# 105358-3SC002-01-A_IR_extra.net
KiCad netlist of a schematic drawn in Altium Designer
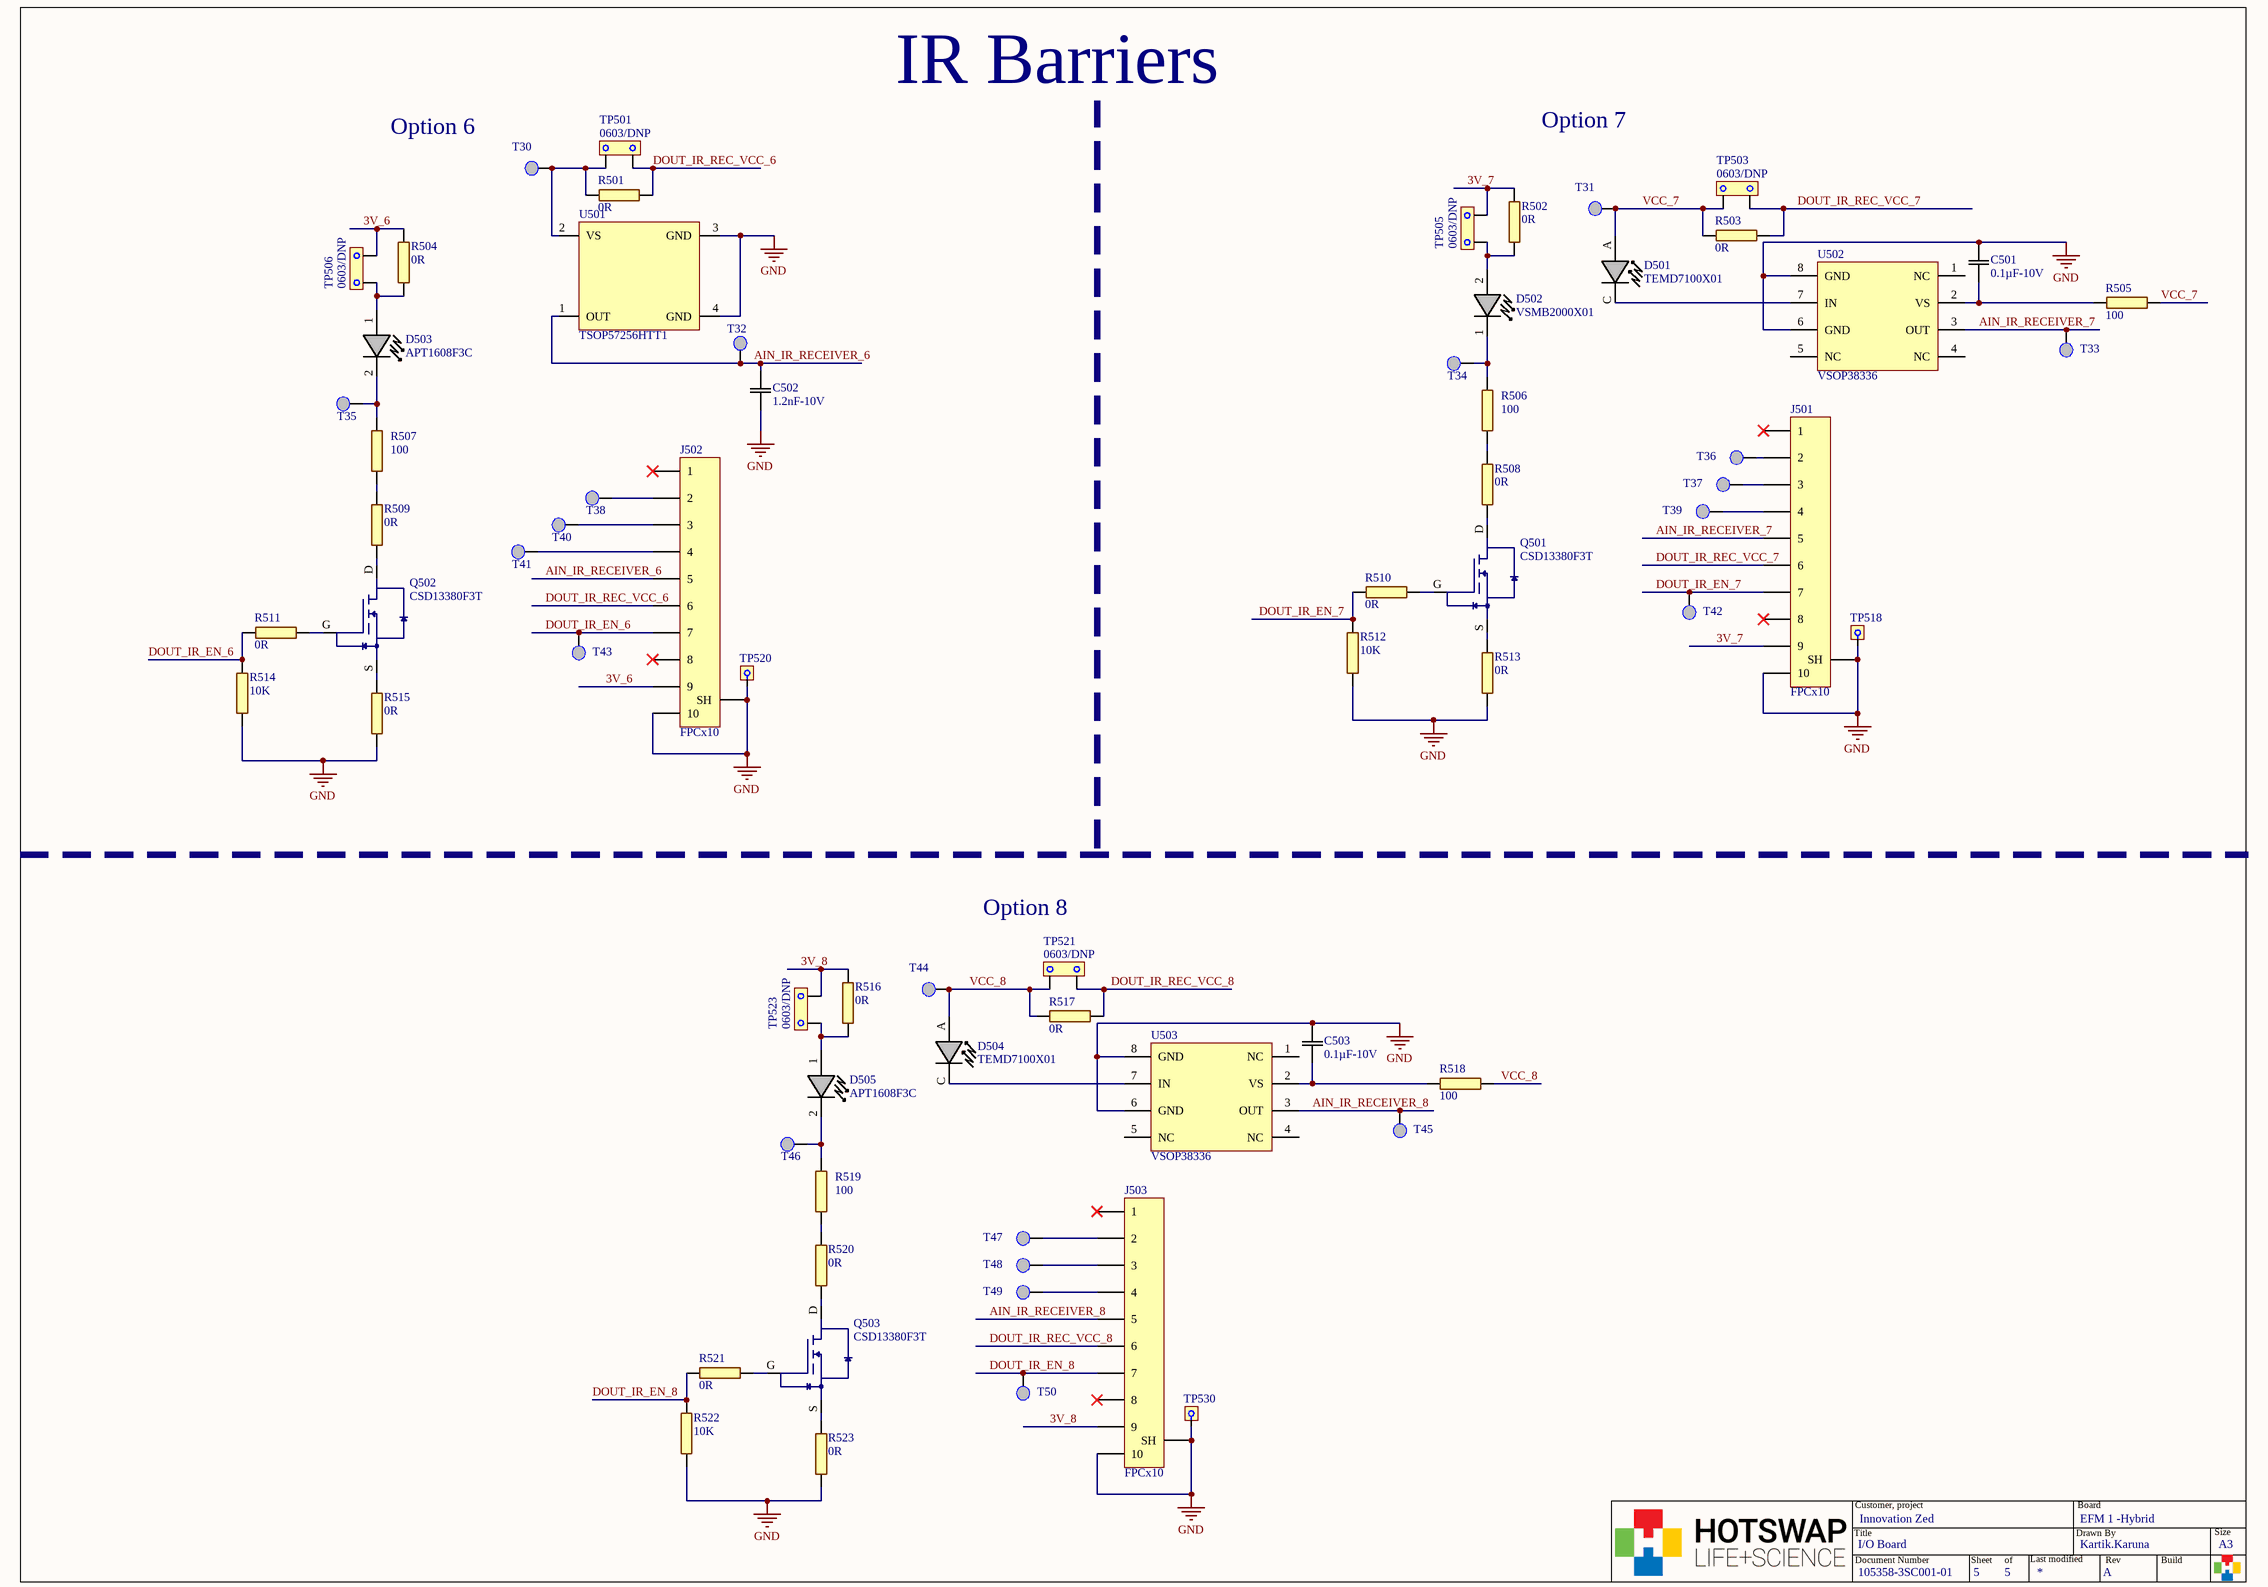
[diagram p0: 105358-3SC002-01-A_IR_extra.SchDoc]

(export (version "E")
  (design (tool "Eeschema 10.0.6"))
  (components
    (comp (ref "C501")
      (value "0.1µF-10V")
      (footprint "0402C_HIGH_DENSITY")
      (description "0.1µF ±10% 10V X5R Ceramic Capacitor 0402")
      (fields
        (field (name "MANUFACTURER PART NUMBER") "CC0402KRX5R6BB104")
        (field (name "MANUFACTURER") "Yageo")
      )
      (libsource (lib "ConnectMedical") (part "0402C-0.1uF-10V"))
    )
    (comp (ref "C502")
      (value "1.2nF-10V")
      (footprint "0402C_HIGH_DENSITY")
      (description "1.2nF ±10% 10V U2J Ceramic Capacitor 0402")
      (fields
        (field (name "MANUFACTURER PART NUMBER") "GRM1557U1A122JA01D")
        (field (name "MANUFACTURER") "Murata Electronics North America")
      )
      (libsource (lib "ConnectMedical") (part "0402C-1.2nF-10V"))
    )
    (comp (ref "C503")
      (value "0.1µF-10V")
      (footprint "0402C_HIGH_DENSITY")
      (description "0.1µF ±10% 10V X5R Ceramic Capacitor 0402")
      (fields
        (field (name "MANUFACTURER PART NUMBER") "CC0402KRX5R6BB104")
        (field (name "MANUFACTURER") "Yageo")
      )
      (libsource (lib "ConnectMedical") (part "0402C-0.1uF-10V"))
    )
    (comp (ref "D501")
      (value "TEMD7100X01")
      (footprint "TEMD7100X01")
      (description "PHOTODIODE PIN 950NM 0805")
      (fields
        (field (name "MANUFACTURER") "Vishay Semiconductor Opto Division")
        (field (name "DIGI-KEY PART NUMBER") "TEMD7100X01CT-ND")
      )
      (libsource (lib "ConnectMedical") (part "TEMD7100X01"))
    )
    (comp (ref "D502")
      (value "VSMB2000X01")
      (footprint "SODFL580X160")
      (description "EMITTER IR 940NM 100MA SMD")
      (fields
        (field (name "MANUFACTURER") "Vishay Semiconductor Opto Division")
        (field (name "DIGI-KEY PART NUMBER") "VSMB2000X01CT-ND")
      )
      (libsource (lib "ConnectMedical") (part "VSMB2000X01"))
    )
    (comp (ref "D503")
      (value "APT1608F3C")
      (footprint "APT1608F3C")
      (description "0603 INFRARED DIODE")
      (fields
        (field (name "MANUFACTURER") "Kingbright")
        (field (name "DIGI-KEY PART NUMBER") "754-1433-1-ND")
      )
      (libsource (lib "ConnectMedical") (part "APT1608F3C"))
    )
    (comp (ref "D504")
      (value "TEMD7100X01")
      (footprint "TEMD7100X01")
      (description "PHOTODIODE PIN 950NM 0805")
      (fields
        (field (name "MANUFACTURER") "Vishay Semiconductor Opto Division")
        (field (name "DIGI-KEY PART NUMBER") "TEMD7100X01CT-ND")
      )
      (libsource (lib "ConnectMedical") (part "TEMD7100X01"))
    )
    (comp (ref "D505")
      (value "APT1608F3C")
      (footprint "APT1608F3C")
      (description "0603 INFRARED DIODE")
      (fields
        (field (name "MANUFACTURER") "Kingbright")
        (field (name "DIGI-KEY PART NUMBER") "754-1433-1-ND")
      )
      (libsource (lib "ConnectMedical") (part "APT1608F3C"))
    )
    (comp (ref "J501")
      (value "FPCx10")
      (footprint "FPCx10-5034801000")
      (description "CONN FFC FPC 10POS 0.50MM R/A")
      (fields
        (field (name "MANUFACTURER PART NUMBER") "5034801000")
        (field (name "MANUFACTURER") "Molex, LLC")
      )
      (libsource (lib "ConnectMedical") (part "FPCx10"))
    )
    (comp (ref "J502")
      (value "FPCx10")
      (footprint "FPCx10-5034801000")
      (description "CONN FFC FPC 10POS 0.50MM R/A")
      (fields
        (field (name "MANUFACTURER PART NUMBER") "5034801000")
        (field (name "MANUFACTURER") "Molex, LLC")
      )
      (libsource (lib "ConnectMedical") (part "FPCx10"))
    )
    (comp (ref "J503")
      (value "FPCx10")
      (footprint "FPCx10-5034801000")
      (description "CONN FFC FPC 10POS 0.50MM R/A")
      (fields
        (field (name "MANUFACTURER PART NUMBER") "5034801000")
        (field (name "MANUFACTURER") "Molex, LLC")
      )
      (libsource (lib "ConnectMedical") (part "FPCx10"))
    )
    (comp (ref "Q501")
      (value "CSD13380F3T")
      (footprint "CSD13380F3-DFN40P69X35-3L")
      (description "12V N-CHANNEL FEMTOFET MOSFET")
      (fields (field (name "MANUFACTURER") "Texas Instruments"))
      (libsource (lib "ConnectMedical") (part "CSD13380F3T"))
    )
    (comp (ref "Q502")
      (value "CSD13380F3T")
      (footprint "CSD13380F3-DFN40P69X35-3L")
      (description "12V N-CHANNEL FEMTOFET MOSFET")
      (fields (field (name "MANUFACTURER") "Texas Instruments"))
      (libsource (lib "ConnectMedical") (part "CSD13380F3T"))
    )
    (comp (ref "Q503")
      (value "CSD13380F3T")
      (footprint "CSD13380F3-DFN40P69X35-3L")
      (description "12V N-CHANNEL FEMTOFET MOSFET")
      (fields (field (name "MANUFACTURER") "Texas Instruments"))
      (libsource (lib "ConnectMedical") (part "CSD13380F3T"))
    )
    (comp (ref "R501")
      (value "0R")
      (footprint "0603R-GENRIC")
      (description "RES SMD 0 OHM 1% 1/10W 0603")
      (fields (field (name "POWER") "0.063W"))
      (libsource (lib "") (part "0603R-0R -1%-0.063W_1"))
    )
    (comp (ref "R502")
      (value "0R")
      (footprint "0603R-GENRIC")
      (description "RES SMD 0 OHM 1% 1/10W 0603")
      (fields (field (name "POWER") "0.063W"))
      (libsource (lib "ConnectMedical") (part "0603R-0R -1%-0.063W"))
    )
    (comp (ref "R503")
      (value "0R")
      (footprint "0603R-GENRIC")
      (description "RES SMD 0 OHM 1% 1/10W 0603")
      (fields (field (name "POWER") "0.063W"))
      (libsource (lib "") (part "0603R-0R -1%-0.063W_1"))
    )
    (comp (ref "R504")
      (value "0R")
      (footprint "0603R-GENRIC")
      (description "RES SMD 0 OHM 1% 1/10W 0603")
      (fields (field (name "POWER") "0.063W"))
      (libsource (lib "ConnectMedical") (part "0603R-0R -1%-0.063W"))
    )
    (comp (ref "R505")
      (value "100")
      (footprint "0402R-GENERIC")
      (description "RES SMD 100OHM 1% 1/16W 0402")
      (fields (field (name "DIGI-KEY PART NUMBER") "311-100LRCT-ND") (field (name "MANUFACTURER") "Yageo"))
      (libsource (lib "ConnectMedical") (part "0402R-100 OHM-1%-0.063W"))
    )
    (comp (ref "R506")
      (value "100")
      (footprint "0402R-GENERIC")
      (description "RES SMD 100OHM 1% 1/16W 0402")
      (fields (field (name "DIGI-KEY PART NUMBER") "311-100LRCT-ND") (field (name "MANUFACTURER") "Yageo"))
      (libsource (lib "") (part "0402R-100 OHM-1%-0.063W_1"))
    )
    (comp (ref "R507")
      (value "100")
      (footprint "0402R-GENERIC")
      (description "RES SMD 100OHM 1% 1/16W 0402")
      (fields (field (name "DIGI-KEY PART NUMBER") "311-100LRCT-ND") (field (name "MANUFACTURER") "Yageo"))
      (libsource (lib "") (part "0402R-100 OHM-1%-0.063W_1"))
    )
    (comp (ref "R508")
      (value "0R")
      (footprint "0603R-GENRIC")
      (description "RES SMD 0 OHM 1% 1/10W 0603")
      (fields (field (name "POWER") "0.063W"))
      (libsource (lib "") (part "0603R-0R -1%-0.063W_2"))
    )
    (comp (ref "R509")
      (value "0R")
      (footprint "0603R-GENRIC")
      (description "RES SMD 0 OHM 1% 1/10W 0603")
      (fields (field (name "POWER") "0.063W"))
      (libsource (lib "") (part "0603R-0R -1%-0.063W_2"))
    )
    (comp (ref "R510")
      (value "0R")
      (footprint "0603R-GENRIC")
      (description "RES SMD 0 OHM 1% 1/10W 0603")
      (fields (field (name "POWER") "0.063W"))
      (libsource (lib "") (part "0603R-0R -1%-0.063W_1"))
    )
    (comp (ref "R511")
      (value "0R")
      (footprint "0603R-GENRIC")
      (description "RES SMD 0 OHM 1% 1/10W 0603")
      (fields (field (name "POWER") "0.063W"))
      (libsource (lib "") (part "0603R-0R -1%-0.063W_1"))
    )
    (comp (ref "R512")
      (value "10K")
      (footprint "0402R-GENERIC")
      (description "RES SMD 10kOHM 1% 1/16W 0402")
      (fields (field (name "DIGI-KEY PART NUMBER") "311-10.0KLRCT-ND") (field (name "MANUFACTURER") "Yageo"))
      (libsource (lib "ConnectMedical") (part "0402R-10k OHM-1%-0.063W"))
    )
    (comp (ref "R513")
      (value "0R")
      (footprint "0603R-GENRIC")
      (description "RES SMD 0 OHM 1% 1/10W 0603")
      (fields (field (name "POWER") "0.063W"))
      (libsource (lib "ConnectMedical") (part "0603R-0R -1%-0.063W"))
    )
    (comp (ref "R514")
      (value "10K")
      (footprint "0402R-GENERIC")
      (description "RES SMD 10kOHM 1% 1/16W 0402")
      (fields (field (name "DIGI-KEY PART NUMBER") "311-10.0KLRCT-ND") (field (name "MANUFACTURER") "Yageo"))
      (libsource (lib "ConnectMedical") (part "0402R-10k OHM-1%-0.063W"))
    )
    (comp (ref "R515")
      (value "0R")
      (footprint "0603R-GENRIC")
      (description "RES SMD 0 OHM 1% 1/10W 0603")
      (fields (field (name "POWER") "0.063W"))
      (libsource (lib "ConnectMedical") (part "0603R-0R -1%-0.063W"))
    )
    (comp (ref "R516")
      (value "0R")
      (footprint "0603R-GENRIC")
      (description "RES SMD 0 OHM 1% 1/10W 0603")
      (fields (field (name "POWER") "0.063W"))
      (libsource (lib "ConnectMedical") (part "0603R-0R -1%-0.063W"))
    )
    (comp (ref "R517")
      (value "0R")
      (footprint "0603R-GENRIC")
      (description "RES SMD 0 OHM 1% 1/10W 0603")
      (fields (field (name "POWER") "0.063W"))
      (libsource (lib "") (part "0603R-0R -1%-0.063W_1"))
    )
    (comp (ref "R518")
      (value "100")
      (footprint "0402R-GENERIC")
      (description "RES SMD 100OHM 1% 1/16W 0402")
      (fields (field (name "DIGI-KEY PART NUMBER") "311-100LRCT-ND") (field (name "MANUFACTURER") "Yageo"))
      (libsource (lib "ConnectMedical") (part "0402R-100 OHM-1%-0.063W"))
    )
    (comp (ref "R519")
      (value "100")
      (footprint "0402R-GENERIC")
      (description "RES SMD 100OHM 1% 1/16W 0402")
      (fields (field (name "DIGI-KEY PART NUMBER") "311-100LRCT-ND") (field (name "MANUFACTURER") "Yageo"))
      (libsource (lib "") (part "0402R-100 OHM-1%-0.063W_1"))
    )
    (comp (ref "R520")
      (value "0R")
      (footprint "0603R-GENRIC")
      (description "RES SMD 0 OHM 1% 1/10W 0603")
      (fields (field (name "POWER") "0.063W"))
      (libsource (lib "") (part "0603R-0R -1%-0.063W_2"))
    )
    (comp (ref "R521")
      (value "0R")
      (footprint "0603R-GENRIC")
      (description "RES SMD 0 OHM 1% 1/10W 0603")
      (fields (field (name "POWER") "0.063W"))
      (libsource (lib "") (part "0603R-0R -1%-0.063W_1"))
    )
    (comp (ref "R522")
      (value "10K")
      (footprint "0402R-GENERIC")
      (description "RES SMD 10kOHM 1% 1/16W 0402")
      (fields (field (name "DIGI-KEY PART NUMBER") "311-10.0KLRCT-ND") (field (name "MANUFACTURER") "Yageo"))
      (libsource (lib "ConnectMedical") (part "0402R-10k OHM-1%-0.063W"))
    )
    (comp (ref "R523")
      (value "0R")
      (footprint "0603R-GENRIC")
      (description "RES SMD 0 OHM 1% 1/10W 0603")
      (fields (field (name "POWER") "0.063W"))
      (libsource (lib "ConnectMedical") (part "0603R-0R -1%-0.063W"))
    )
    (comp (ref "T30")
      (value "TEST POINT")
      (footprint "PAD TEST POINT")
      (description "Testing Poiny")
      (libsource (lib "ConnectMedical") (part "TEST POINT"))
    )
    (comp (ref "T31")
      (value "TEST POINT")
      (footprint "PAD TEST POINT")
      (description "Testing Poiny")
      (libsource (lib "ConnectMedical") (part "TEST POINT"))
    )
    (comp (ref "T32")
      (value "TEST POINT")
      (footprint "PAD TEST POINT")
      (description "Testing Poiny")
      (libsource (lib "ConnectMedical") (part "TEST POINT"))
    )
    (comp (ref "T33")
      (value "TEST POINT")
      (footprint "PAD TEST POINT")
      (description "Testing Poiny")
      (libsource (lib "ConnectMedical") (part "TEST POINT"))
    )
    (comp (ref "T34")
      (value "TEST POINT")
      (footprint "PAD TEST POINT")
      (description "Testing Poiny")
      (libsource (lib "ConnectMedical") (part "TEST POINT"))
    )
    (comp (ref "T35")
      (value "TEST POINT")
      (footprint "PAD TEST POINT")
      (description "Testing Poiny")
      (libsource (lib "ConnectMedical") (part "TEST POINT"))
    )
    (comp (ref "T36")
      (value "TEST POINT")
      (footprint "PAD TEST POINT")
      (description "Testing Poiny")
      (libsource (lib "ConnectMedical") (part "TEST POINT"))
    )
    (comp (ref "T37")
      (value "TEST POINT")
      (footprint "PAD TEST POINT")
      (description "Testing Poiny")
      (libsource (lib "ConnectMedical") (part "TEST POINT"))
    )
    (comp (ref "T38")
      (value "TEST POINT")
      (footprint "PAD TEST POINT")
      (description "Testing Poiny")
      (libsource (lib "ConnectMedical") (part "TEST POINT"))
    )
    (comp (ref "T39")
      (value "TEST POINT")
      (footprint "PAD TEST POINT")
      (description "Testing Poiny")
      (libsource (lib "ConnectMedical") (part "TEST POINT"))
    )
    (comp (ref "T40")
      (value "TEST POINT")
      (footprint "PAD TEST POINT")
      (description "Testing Poiny")
      (libsource (lib "ConnectMedical") (part "TEST POINT"))
    )
    (comp (ref "T41")
      (value "TEST POINT")
      (footprint "PAD TEST POINT")
      (description "Testing Poiny")
      (libsource (lib "ConnectMedical") (part "TEST POINT"))
    )
    (comp (ref "T42")
      (value "TEST POINT")
      (footprint "PAD TEST POINT")
      (description "Testing Poiny")
      (libsource (lib "ConnectMedical") (part "TEST POINT"))
    )
    (comp (ref "T43")
      (value "TEST POINT")
      (footprint "PAD TEST POINT")
      (description "Testing Poiny")
      (libsource (lib "ConnectMedical") (part "TEST POINT"))
    )
    (comp (ref "T44")
      (value "TEST POINT")
      (footprint "PAD TEST POINT")
      (description "Testing Poiny")
      (libsource (lib "ConnectMedical") (part "TEST POINT"))
    )
    (comp (ref "T45")
      (value "TEST POINT")
      (footprint "PAD TEST POINT")
      (description "Testing Poiny")
      (libsource (lib "ConnectMedical") (part "TEST POINT"))
    )
    (comp (ref "T46")
      (value "TEST POINT")
      (footprint "PAD TEST POINT")
      (description "Testing Poiny")
      (libsource (lib "ConnectMedical") (part "TEST POINT"))
    )
    (comp (ref "T47")
      (value "TEST POINT")
      (footprint "PAD TEST POINT")
      (description "Testing Poiny")
      (libsource (lib "ConnectMedical") (part "TEST POINT"))
    )
    (comp (ref "T48")
      (value "TEST POINT")
      (footprint "PAD TEST POINT")
      (description "Testing Poiny")
      (libsource (lib "ConnectMedical") (part "TEST POINT"))
    )
    (comp (ref "T49")
      (value "TEST POINT")
      (footprint "PAD TEST POINT")
      (description "Testing Poiny")
      (libsource (lib "ConnectMedical") (part "TEST POINT"))
    )
    (comp (ref "T50")
      (value "TEST POINT")
      (footprint "PAD TEST POINT")
      (description "Testing Poiny")
      (libsource (lib "ConnectMedical") (part "TEST POINT"))
    )
    (comp (ref "TP501")
      (value "0603/DNP")
      (footprint "TESTPOINT_C_R0608")
      (description "Test point for Med Current 0402 JUMPER SMD O OHM 1% 1/4W 0603")
      (libsource (lib "") (part "TP_C_R0603_1"))
    )
    (comp (ref "TP503")
      (value "0603/DNP")
      (footprint "TESTPOINT_C_R0608")
      (description "Test point for Med Current 0402 JUMPER SMD O OHM 1% 1/4W 0603")
      (libsource (lib "") (part "TP_C_R0603_1"))
    )
    (comp (ref "TP505")
      (value "0603/DNP")
      (footprint "TESTPOINT_C_R0608")
      (description "Test point for Med Current 0402 JUMPER SMD O OHM 1% 1/4W 0603")
      (libsource (lib "ConnectMedical") (part "TP_C_R0603"))
    )
    (comp (ref "TP506")
      (value "0603/DNP")
      (footprint "TESTPOINT_C_R0608")
      (description "Test point for Med Current 0402 JUMPER SMD O OHM 1% 1/4W 0603")
      (libsource (lib "ConnectMedical") (part "TP_C_R0603"))
    )
    (comp (ref "TP518")
      (value "TP_V_HOOK")
      (footprint "Testpoint_Hook")
      (description "Black PC Test Point")
      (fields
        (field (name "DIGI-KEY PART NUMBER") "36-5001-ND")
        (field (name "MANUFACTURER") "Keystone Electronics")
      )
      (libsource (lib "ConnectMedical") (part "TP_V_HOOK"))
    )
    (comp (ref "TP520")
      (value "TP_V_HOOK")
      (footprint "Testpoint_Hook")
      (description "Black PC Test Point")
      (fields
        (field (name "DIGI-KEY PART NUMBER") "36-5001-ND")
        (field (name "MANUFACTURER") "Keystone Electronics")
      )
      (libsource (lib "ConnectMedical") (part "TP_V_HOOK"))
    )
    (comp (ref "TP521")
      (value "0603/DNP")
      (footprint "TESTPOINT_C_R0608")
      (description "Test point for Med Current 0402 JUMPER SMD O OHM 1% 1/4W 0603")
      (libsource (lib "") (part "TP_C_R0603_1"))
    )
    (comp (ref "TP523")
      (value "0603/DNP")
      (footprint "TESTPOINT_C_R0608")
      (description "Test point for Med Current 0402 JUMPER SMD O OHM 1% 1/4W 0603")
      (libsource (lib "ConnectMedical") (part "TP_C_R0603"))
    )
    (comp (ref "TP530")
      (value "TP_V_HOOK")
      (footprint "Testpoint_Hook")
      (description "Black PC Test Point")
      (fields
        (field (name "DIGI-KEY PART NUMBER") "36-5001-ND")
        (field (name "MANUFACTURER") "Keystone Electronics")
      )
      (libsource (lib "ConnectMedical") (part "TP_V_HOOK"))
    )
    (comp (ref "U501")
      (value "TSOP57256HTT1")
      (footprint "TSOP57256HTT1")
      (description "MOD IR RCVR 56KHZ TOP VIEW SHIEL")
      (fields
        (field (name "MANUFACTURER") "Vishay Semiconductor Opto Division")
        (field (name "DIGI-KEY PART NUMBER") "TSOP57256HTT1-ND")
      )
      (libsource (lib "ConnectMedical") (part "TSOP57256HTT1"))
    )
    (comp (ref "U502")
      (value "VSOP38336")
      (footprint "VSOP38336")
      (description "IC SIGNAL CONDITIONING 36KHZ QFN")
      (fields
        (field (name "MANUFACTURER") "Vishay Semiconductor Opto Division")
        (field (name "DIGI-KEY PART NUMBER") "VSOP38336CT-ND")
      )
      (libsource (lib "ConnectMedical") (part "VSOP38336"))
    )
    (comp (ref "U503")
      (value "VSOP38336")
      (footprint "VSOP38336")
      (description "IC SIGNAL CONDITIONING 36KHZ QFN")
      (fields
        (field (name "MANUFACTURER") "Vishay Semiconductor Opto Division")
        (field (name "DIGI-KEY PART NUMBER") "VSOP38336CT-ND")
      )
      (libsource (lib "ConnectMedical") (part "VSOP38336"))
    )
  )
  (nets
    (net (code "1") (name "/3V_6") (class "Default")
      (node (ref "J502") (pin "9") (pinfunction "9_9") (pintype "passive"))
      (node (ref "R504") (pin "2") (pintype "passive"))
      (node (ref "TP506") (pin "2") (pintype "power_in"))
    )
    (net (code "2") (name "/3V_7") (class "Default")
      (node (ref "J501") (pin "9") (pinfunction "9_9") (pintype "passive"))
      (node (ref "R502") (pin "2") (pintype "passive"))
      (node (ref "TP505") (pin "2") (pintype "power_in"))
    )
    (net (code "3") (name "/3V_8") (class "Default")
      (node (ref "J503") (pin "9") (pinfunction "9_9") (pintype "passive"))
      (node (ref "R516") (pin "2") (pintype "passive"))
      (node (ref "TP523") (pin "2") (pintype "power_in"))
    )
    (net (code "4") (name "/AIN_IR_RECEIVER_6") (class "Default")
      (node (ref "C502") (pin "2") (pinfunction "2_2") (pintype "passive"))
      (node (ref "J502") (pin "5") (pinfunction "5_5") (pintype "passive"))
      (node (ref "T32") (pin "1") (pinfunction "Test_Point_1") (pintype "passive"))
      (node (ref "U501") (pin "1") (pinfunction "OUT_1") (pintype "power_in"))
    )
    (net (code "5") (name "/AIN_IR_RECEIVER_7") (class "Default")
      (node (ref "J501") (pin "5") (pinfunction "5_5") (pintype "passive"))
      (node (ref "T33") (pin "1") (pinfunction "Test_Point_1") (pintype "passive"))
      (node (ref "U502") (pin "3") (pinfunction "OUT_3") (pintype "passive"))
    )
    (net (code "6") (name "/AIN_IR_RECEIVER_8") (class "Default")
      (node (ref "J503") (pin "5") (pinfunction "5_5") (pintype "passive"))
      (node (ref "T45") (pin "1") (pinfunction "Test_Point_1") (pintype "passive"))
      (node (ref "U503") (pin "3") (pinfunction "OUT_3") (pintype "passive"))
    )
    (net (code "7") (name "/DOUT_IR_EN_6") (class "Default")
      (node (ref "J502") (pin "7") (pinfunction "7_7") (pintype "passive"))
      (node (ref "R511") (pin "1") (pintype "passive"))
      (node (ref "R514") (pin "1") (pintype "passive"))
      (node (ref "T43") (pin "1") (pinfunction "Test_Point_1") (pintype "passive"))
    )
    (net (code "8") (name "/DOUT_IR_EN_7") (class "Default")
      (node (ref "J501") (pin "7") (pinfunction "7_7") (pintype "passive"))
      (node (ref "R510") (pin "1") (pintype "passive"))
      (node (ref "R512") (pin "1") (pintype "passive"))
      (node (ref "T42") (pin "1") (pinfunction "Test_Point_1") (pintype "passive"))
    )
    (net (code "9") (name "/DOUT_IR_EN_8") (class "Default")
      (node (ref "J503") (pin "7") (pinfunction "7_7") (pintype "passive"))
      (node (ref "R521") (pin "1") (pintype "passive"))
      (node (ref "R522") (pin "1") (pintype "passive"))
      (node (ref "T50") (pin "1") (pinfunction "Test_Point_1") (pintype "passive"))
    )
    (net (code "10") (name "/DOUT_IR_REC_VCC_6") (class "Default")
      (node (ref "J502") (pin "6") (pinfunction "6_6") (pintype "passive"))
      (node (ref "R501") (pin "2") (pintype "passive"))
      (node (ref "TP501") (pin "2") (pintype "power_in"))
    )
    (net (code "11") (name "/DOUT_IR_REC_VCC_7") (class "Default")
      (node (ref "J501") (pin "6") (pinfunction "6_6") (pintype "passive"))
      (node (ref "R503") (pin "2") (pintype "passive"))
      (node (ref "TP503") (pin "2") (pintype "power_in"))
    )
    (net (code "12") (name "/DOUT_IR_REC_VCC_8") (class "Default")
      (node (ref "J503") (pin "6") (pinfunction "6_6") (pintype "passive"))
      (node (ref "R517") (pin "2") (pintype "passive"))
      (node (ref "TP521") (pin "2") (pintype "power_in"))
    )
    (net (code "13") (name "/VCC_7") (class "Default")
      (node (ref "D501") (pin "A") (pinfunction "A_A") (pintype "passive"))
      (node (ref "R503") (pin "1") (pintype "passive"))
      (node (ref "R505") (pin "2") (pintype "passive"))
      (node (ref "T31") (pin "1") (pinfunction "Test_Point_1") (pintype "passive"))
      (node (ref "TP503") (pin "1") (pintype "power_in"))
    )
    (net (code "14") (name "/VCC_8") (class "Default")
      (node (ref "D504") (pin "A") (pinfunction "A_A") (pintype "passive"))
      (node (ref "R517") (pin "1") (pintype "passive"))
      (node (ref "R518") (pin "2") (pintype "passive"))
      (node (ref "T44") (pin "1") (pinfunction "Test_Point_1") (pintype "passive"))
      (node (ref "TP521") (pin "1") (pintype "power_in"))
    )
    (net (code "15") (name "GND") (class "Default")
      (node (ref "C501") (pin "2") (pinfunction "2_2") (pintype "passive"))
      (node (ref "C502") (pin "1") (pinfunction "1_1") (pintype "passive"))
      (node (ref "C503") (pin "2") (pinfunction "2_2") (pintype "passive"))
      (node (ref "J501") (pin "10") (pinfunction "10_10") (pintype "passive"))
      (node (ref "J501") (pin "SH") (pinfunction "SH_SH") (pintype "passive"))
      (node (ref "J502") (pin "10") (pinfunction "10_10") (pintype "passive"))
      (node (ref "J502") (pin "SH") (pinfunction "SH_SH") (pintype "passive"))
      (node (ref "J503") (pin "10") (pinfunction "10_10") (pintype "passive"))
      (node (ref "J503") (pin "SH") (pinfunction "SH_SH") (pintype "passive"))
      (node (ref "R512") (pin "2") (pintype "passive"))
      (node (ref "R513") (pin "1") (pintype "passive"))
      (node (ref "R514") (pin "2") (pintype "passive"))
      (node (ref "R515") (pin "1") (pintype "passive"))
      (node (ref "R522") (pin "2") (pintype "passive"))
      (node (ref "R523") (pin "1") (pintype "passive"))
      (node (ref "TP518") (pin "1") (pinfunction "8_1") (pintype "passive"))
      (node (ref "TP520") (pin "1") (pinfunction "8_1") (pintype "passive"))
      (node (ref "TP530") (pin "1") (pinfunction "8_1") (pintype "passive"))
      (node (ref "U501") (pin "3") (pinfunction "GND_3") (pintype "passive"))
      (node (ref "U501") (pin "4") (pinfunction "GND_4") (pintype "passive"))
      (node (ref "U502") (pin "6") (pinfunction "GND_6") (pintype "passive"))
      (node (ref "U502") (pin "8") (pinfunction "GND_8") (pintype "passive"))
      (node (ref "U503") (pin "6") (pinfunction "GND_6") (pintype "passive"))
      (node (ref "U503") (pin "8") (pinfunction "GND_8") (pintype "passive"))
    )
    (net (code "16") (name "Net-(D502-A)") (class "Default")
      (node (ref "D502") (pin "2") (pinfunction "A_2") (pintype "passive"))
      (node (ref "R502") (pin "1") (pintype "passive"))
      (node (ref "TP505") (pin "1") (pintype "power_in"))
    )
    (net (code "17") (name "Net-(D502-C)") (class "Default")
      (node (ref "D502") (pin "1") (pinfunction "C_1") (pintype "passive"))
      (node (ref "R506") (pin "1") (pintype "passive"))
      (node (ref "T34") (pin "1") (pinfunction "Test_Point_1") (pintype "passive"))
    )
    (net (code "18") (name "Net-(D503-A)") (class "Default")
      (node (ref "D503") (pin "1") (pinfunction "A_1") (pintype "passive"))
      (node (ref "R504") (pin "1") (pintype "passive"))
      (node (ref "TP506") (pin "1") (pintype "power_in"))
    )
    (net (code "19") (name "Net-(D503-K)") (class "Default")
      (node (ref "D503") (pin "2") (pinfunction "K_2") (pintype "passive"))
      (node (ref "R507") (pin "1") (pintype "passive"))
      (node (ref "T35") (pin "1") (pinfunction "Test_Point_1") (pintype "passive"))
    )
    (net (code "20") (name "Net-(D505-A)") (class "Default")
      (node (ref "D505") (pin "1") (pinfunction "A_1") (pintype "passive"))
      (node (ref "R516") (pin "1") (pintype "passive"))
      (node (ref "TP523") (pin "1") (pintype "power_in"))
    )
    (net (code "21") (name "Net-(D505-K)") (class "Default")
      (node (ref "D505") (pin "2") (pinfunction "K_2") (pintype "passive"))
      (node (ref "R519") (pin "1") (pintype "passive"))
      (node (ref "T46") (pin "1") (pinfunction "Test_Point_1") (pintype "passive"))
    )
    (net (code "22") (name "Net-(Q501-1)") (class "Default")
      (node (ref "Q501") (pin "G") (pinfunction "1_G") (pintype "passive"))
      (node (ref "R510") (pin "2") (pintype "passive"))
    )
    (net (code "23") (name "Net-(Q501-2)") (class "Default")
      (node (ref "Q501") (pin "S") (pinfunction "2_S") (pintype "passive"))
      (node (ref "R513") (pin "2") (pintype "passive"))
    )
    (net (code "24") (name "Net-(Q501-3)") (class "Default")
      (node (ref "Q501") (pin "D") (pinfunction "3_D") (pintype "passive"))
      (node (ref "R508") (pin "2") (pintype "passive"))
    )
    (net (code "25") (name "Net-(Q502-1)") (class "Default")
      (node (ref "Q502") (pin "G") (pinfunction "1_G") (pintype "passive"))
      (node (ref "R511") (pin "2") (pintype "passive"))
    )
    (net (code "26") (name "Net-(Q502-2)") (class "Default")
      (node (ref "Q502") (pin "S") (pinfunction "2_S") (pintype "passive"))
      (node (ref "R515") (pin "2") (pintype "passive"))
    )
    (net (code "27") (name "Net-(Q502-3)") (class "Default")
      (node (ref "Q502") (pin "D") (pinfunction "3_D") (pintype "passive"))
      (node (ref "R509") (pin "2") (pintype "passive"))
    )
    (net (code "28") (name "Net-(Q503-1)") (class "Default")
      (node (ref "Q503") (pin "G") (pinfunction "1_G") (pintype "passive"))
      (node (ref "R521") (pin "2") (pintype "passive"))
    )
    (net (code "29") (name "Net-(Q503-2)") (class "Default")
      (node (ref "Q503") (pin "S") (pinfunction "2_S") (pintype "passive"))
      (node (ref "R523") (pin "2") (pintype "passive"))
    )
    (net (code "30") (name "Net-(Q503-3)") (class "Default")
      (node (ref "Q503") (pin "D") (pinfunction "3_D") (pintype "passive"))
      (node (ref "R520") (pin "2") (pintype "passive"))
    )
    (net (code "31") (name "Net-(R506-Pad2)") (class "Default")
      (node (ref "R506") (pin "2") (pintype "passive"))
      (node (ref "R508") (pin "1") (pintype "passive"))
    )
    (net (code "32") (name "Net-(R507-Pad2)") (class "Default")
      (node (ref "R507") (pin "2") (pintype "passive"))
      (node (ref "R509") (pin "1") (pintype "passive"))
    )
    (net (code "33") (name "Net-(R519-Pad2)") (class "Default")
      (node (ref "R519") (pin "2") (pintype "passive"))
      (node (ref "R520") (pin "1") (pintype "passive"))
    )
    (net (code "34") (name "Net-(T30-Test_Point)") (class "Default")
      (node (ref "R501") (pin "1") (pintype "passive"))
      (node (ref "T30") (pin "1") (pinfunction "Test_Point_1") (pintype "passive"))
      (node (ref "TP501") (pin "1") (pintype "power_in"))
      (node (ref "U501") (pin "2") (pinfunction "VS_2") (pintype "passive"))
    )
    (net (code "35") (name "Net-(T36-Test_Point)") (class "Default")
      (node (ref "J501") (pin "2") (pinfunction "2_2") (pintype "passive"))
      (node (ref "T36") (pin "1") (pinfunction "Test_Point_1") (pintype "passive"))
    )
    (net (code "36") (name "Net-(T37-Test_Point)") (class "Default")
      (node (ref "J501") (pin "3") (pinfunction "3_3") (pintype "passive"))
      (node (ref "T37") (pin "1") (pinfunction "Test_Point_1") (pintype "passive"))
    )
    (net (code "37") (name "Net-(T38-Test_Point)") (class "Default")
      (node (ref "J502") (pin "2") (pinfunction "2_2") (pintype "passive"))
      (node (ref "T38") (pin "1") (pinfunction "Test_Point_1") (pintype "passive"))
    )
    (net (code "38") (name "Net-(T39-Test_Point)") (class "Default")
      (node (ref "J501") (pin "4") (pinfunction "4_4") (pintype "passive"))
      (node (ref "T39") (pin "1") (pinfunction "Test_Point_1") (pintype "passive"))
    )
    (net (code "39") (name "Net-(T40-Test_Point)") (class "Default")
      (node (ref "J502") (pin "3") (pinfunction "3_3") (pintype "passive"))
      (node (ref "T40") (pin "1") (pinfunction "Test_Point_1") (pintype "passive"))
    )
    (net (code "40") (name "Net-(T41-Test_Point)") (class "Default")
      (node (ref "J502") (pin "4") (pinfunction "4_4") (pintype "passive"))
      (node (ref "T41") (pin "1") (pinfunction "Test_Point_1") (pintype "passive"))
    )
    (net (code "41") (name "Net-(T47-Test_Point)") (class "Default")
      (node (ref "J503") (pin "2") (pinfunction "2_2") (pintype "passive"))
      (node (ref "T47") (pin "1") (pinfunction "Test_Point_1") (pintype "passive"))
    )
    (net (code "42") (name "Net-(T48-Test_Point)") (class "Default")
      (node (ref "J503") (pin "3") (pinfunction "3_3") (pintype "passive"))
      (node (ref "T48") (pin "1") (pinfunction "Test_Point_1") (pintype "passive"))
    )
    (net (code "43") (name "Net-(T49-Test_Point)") (class "Default")
      (node (ref "J503") (pin "4") (pinfunction "4_4") (pintype "passive"))
      (node (ref "T49") (pin "1") (pinfunction "Test_Point_1") (pintype "passive"))
    )
    (net (code "44") (name "Net-(U502-IN)") (class "Default")
      (node (ref "D501") (pin "C") (pinfunction "C_C") (pintype "passive"))
      (node (ref "U502") (pin "7") (pinfunction "IN_7") (pintype "passive"))
    )
    (net (code "45") (name "Net-(U502-VS)") (class "Default")
      (node (ref "C501") (pin "1") (pinfunction "1_1") (pintype "passive"))
      (node (ref "R505") (pin "1") (pintype "passive"))
      (node (ref "U502") (pin "2") (pinfunction "VS_2") (pintype "passive"))
    )
    (net (code "46") (name "Net-(U503-IN)") (class "Default")
      (node (ref "D504") (pin "C") (pinfunction "C_C") (pintype "passive"))
      (node (ref "U503") (pin "7") (pinfunction "IN_7") (pintype "passive"))
    )
    (net (code "47") (name "Net-(U503-VS)") (class "Default")
      (node (ref "C503") (pin "1") (pinfunction "1_1") (pintype "passive"))
      (node (ref "R518") (pin "1") (pintype "passive"))
      (node (ref "U503") (pin "2") (pinfunction "VS_2") (pintype "passive"))
    )
    (net (code "48") (name "unconnected-(J501-Pad1)") (class "Default")
      (node (ref "J501") (pin "1") (pinfunction "1_1") (pintype "passive+no_connect"))
    )
    (net (code "49") (name "unconnected-(J501-Pad8)") (class "Default")
      (node (ref "J501") (pin "8") (pinfunction "8_8") (pintype "passive+no_connect"))
    )
    (net (code "50") (name "unconnected-(J502-Pad1)") (class "Default")
      (node (ref "J502") (pin "1") (pinfunction "1_1") (pintype "passive+no_connect"))
    )
    (net (code "51") (name "unconnected-(J502-Pad8)") (class "Default")
      (node (ref "J502") (pin "8") (pinfunction "8_8") (pintype "passive+no_connect"))
    )
    (net (code "52") (name "unconnected-(J503-Pad1)") (class "Default")
      (node (ref "J503") (pin "1") (pinfunction "1_1") (pintype "passive+no_connect"))
    )
    (net (code "53") (name "unconnected-(J503-Pad8)") (class "Default")
      (node (ref "J503") (pin "8") (pinfunction "8_8") (pintype "passive+no_connect"))
    )
    (net (code "54") (name "unconnected-(U502-NC-Pad1)") (class "Default")
      (node (ref "U502") (pin "1") (pinfunction "NC_1") (pintype "passive"))
    )
    (net (code "55") (name "unconnected-(U502-NC-Pad4)") (class "Default")
      (node (ref "U502") (pin "4") (pinfunction "NC_4") (pintype "passive"))
    )
    (net (code "56") (name "unconnected-(U502-NC-Pad5)") (class "Default")
      (node (ref "U502") (pin "5") (pinfunction "NC_5") (pintype "passive"))
    )
    (net (code "57") (name "unconnected-(U503-NC-Pad1)") (class "Default")
      (node (ref "U503") (pin "1") (pinfunction "NC_1") (pintype "passive"))
    )
    (net (code "58") (name "unconnected-(U503-NC-Pad4)") (class "Default")
      (node (ref "U503") (pin "4") (pinfunction "NC_4") (pintype "passive"))
    )
    (net (code "59") (name "unconnected-(U503-NC-Pad5)") (class "Default")
      (node (ref "U503") (pin "5") (pinfunction "NC_5") (pintype "passive"))
    )
  )
)
